# power-distribution.net
KiCad netlist of a schematic drawn in EAGLE
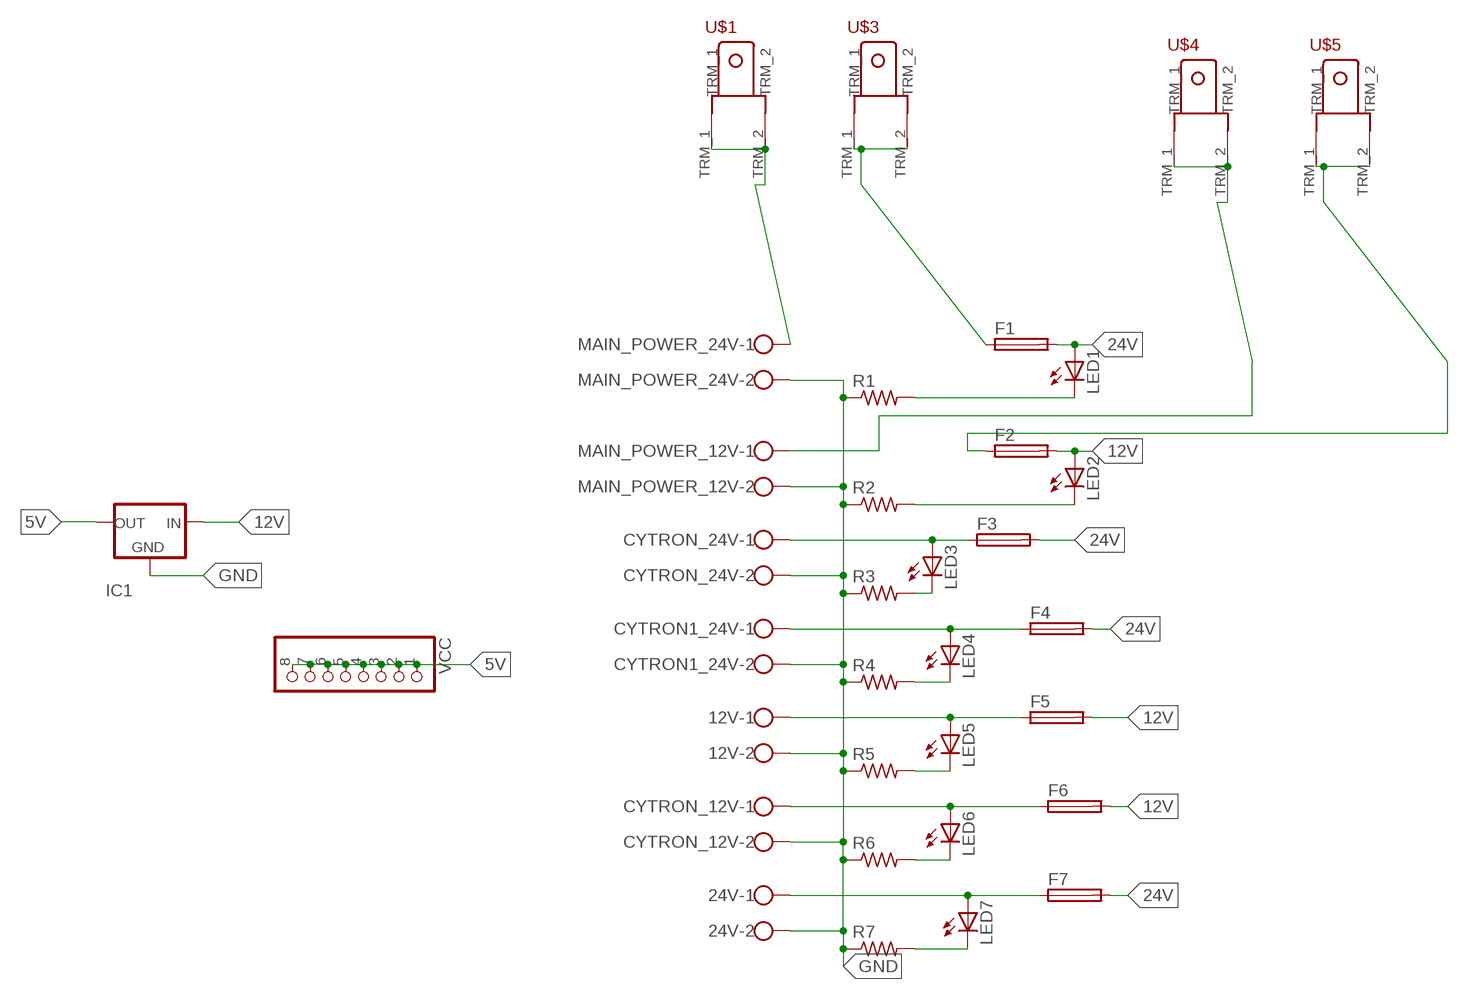
[diagram p0: schematic, sheet 1]

(export (version "E")
  (design (tool "Eeschema 10.0.6"))
  (components
    (comp (ref "12V")
      (value "W237-113")
      (footprint "eagle-import:W237-113")
      (libsource (lib "eagle-import") (part "W237-113"))
    )
    (comp (ref "24V")
      (value "W237-113")
      (footprint "eagle-import:W237-113")
      (libsource (lib "eagle-import") (part "W237-113"))
    )
    (comp (ref "CYTRON1_24V")
      (value "W237-113")
      (footprint "eagle-import:W237-113")
      (libsource (lib "eagle-import") (part "W237-113"))
    )
    (comp (ref "CYTRON_12V")
      (value "W237-113")
      (footprint "eagle-import:W237-113")
      (libsource (lib "eagle-import") (part "W237-113"))
    )
    (comp (ref "CYTRON_24V")
      (value "W237-113")
      (footprint "eagle-import:W237-113")
      (libsource (lib "eagle-import") (part "W237-113"))
    )
    (comp (ref "F1")
      (value "SH22,5A")
      (footprint "eagle-import:SH22,5A")
      (fields (field (name "MPN") "0031.7701.11"))
      (libsource (lib "eagle-import") (part "SH22,5A"))
    )
    (comp (ref "F2")
      (value "SH22,5A")
      (footprint "eagle-import:SH22,5A")
      (fields (field (name "MPN") "0031.7701.11"))
      (libsource (lib "eagle-import") (part "SH22,5A"))
    )
    (comp (ref "F3")
      (value "SH22,5A")
      (footprint "eagle-import:SH22,5A")
      (fields (field (name "MPN") "0031.7701.11"))
      (libsource (lib "eagle-import") (part "SH22,5A"))
    )
    (comp (ref "F4")
      (value "SH22,5A")
      (footprint "eagle-import:SH22,5A")
      (fields (field (name "MPN") "0031.7701.11"))
      (libsource (lib "eagle-import") (part "SH22,5A"))
    )
    (comp (ref "F5")
      (value "SH22,5A")
      (footprint "eagle-import:SH22,5A")
      (fields (field (name "MPN") "0031.7701.11"))
      (libsource (lib "eagle-import") (part "SH22,5A"))
    )
    (comp (ref "F6")
      (value "SH22,5A")
      (footprint "eagle-import:SH22,5A")
      (fields (field (name "MPN") "0031.7701.11"))
      (libsource (lib "eagle-import") (part "SH22,5A"))
    )
    (comp (ref "F7")
      (value "SH22,5A")
      (footprint "eagle-import:SH22,5A")
      (fields (field (name "MPN") "0031.7701.11"))
      (libsource (lib "eagle-import") (part "SH22,5A"))
    )
    (comp (ref "IC1")
      (value "79XX-TO3")
      (footprint "eagle-import:TO3-79")
      (libsource (lib "eagle-import") (part "79XX-TO3"))
    )
    (comp (ref "LED1")
      (value "LED5MM")
      (footprint "eagle-import:LED5MM")
      (libsource (lib "eagle-import") (part "LED5MM"))
    )
    (comp (ref "LED2")
      (value "LED5MM")
      (footprint "eagle-import:LED5MM")
      (libsource (lib "eagle-import") (part "LED5MM"))
    )
    (comp (ref "LED3")
      (value "LED3MM")
      (footprint "eagle-import:LED3MM")
      (libsource (lib "eagle-import") (part "LED3MM"))
    )
    (comp (ref "LED4")
      (value "LED3MM")
      (footprint "eagle-import:LED3MM")
      (libsource (lib "eagle-import") (part "LED3MM"))
    )
    (comp (ref "LED5")
      (value "LED3MM")
      (footprint "eagle-import:LED3MM")
      (libsource (lib "eagle-import") (part "LED3MM"))
    )
    (comp (ref "LED6")
      (value "LED3MM")
      (footprint "eagle-import:LED3MM")
      (libsource (lib "eagle-import") (part "LED3MM"))
    )
    (comp (ref "LED7")
      (value "LED3MM")
      (footprint "eagle-import:LED3MM")
      (libsource (lib "eagle-import") (part "LED3MM"))
    )
    (comp (ref "MAIN_POWER_12V")
      (value "W237-113")
      (footprint "eagle-import:W237-113")
      (libsource (lib "eagle-import") (part "W237-113"))
    )
    (comp (ref "MAIN_POWER_24V")
      (value "W237-113")
      (footprint "eagle-import:W237-113")
      (libsource (lib "eagle-import") (part "W237-113"))
    )
    (comp (ref "R1")
      (value "R-US_0204/5")
      (footprint "eagle-import:0204_5")
      (libsource (lib "eagle-import") (part "R-US_0204/5"))
    )
    (comp (ref "R2")
      (value "R-US_0207/12")
      (footprint "eagle-import:0207_12")
      (libsource (lib "eagle-import") (part "R-US_0207/12"))
    )
    (comp (ref "R3")
      (value "R-US_0204/5")
      (footprint "eagle-import:0204_5")
      (libsource (lib "eagle-import") (part "R-US_0204/5"))
    )
    (comp (ref "R4")
      (value "R-US_0204/5")
      (footprint "eagle-import:0204_5")
      (libsource (lib "eagle-import") (part "R-US_0204/5"))
    )
    (comp (ref "R5")
      (value "R-US_0207/10")
      (footprint "eagle-import:0207_10")
      (libsource (lib "eagle-import") (part "R-US_0207/10"))
    )
    (comp (ref "R6")
      (value "R-US_0204/5")
      (footprint "eagle-import:0204_5")
      (libsource (lib "eagle-import") (part "R-US_0204/5"))
    )
    (comp (ref "R7")
      (value "R-US_0204/5")
      (footprint "eagle-import:0204_5")
      (libsource (lib "eagle-import") (part "R-US_0204/5"))
    )
    (comp (ref "U$1")
      (value "TERMINAL_EDITED")
      (footprint "eagle-import:TERMINAL_EDITED")
      (libsource (lib "eagle-import") (part "TERMINAL_EDITED"))
    )
    (comp (ref "U$3")
      (value "TERMINAL_EDITED")
      (footprint "eagle-import:TERMINAL_EDITED")
      (libsource (lib "eagle-import") (part "TERMINAL_EDITED"))
    )
    (comp (ref "U$4")
      (value "TERMINAL_EDITED")
      (footprint "eagle-import:TERMINAL_EDITED")
      (libsource (lib "eagle-import") (part "TERMINAL_EDITED"))
    )
    (comp (ref "U$5")
      (value "TERMINAL_EDITED")
      (footprint "eagle-import:TERMINAL_EDITED")
      (libsource (lib "eagle-import") (part "TERMINAL_EDITED"))
    )
    (comp (ref "VCC")
      (value "PINHD-1X8")
      (footprint "eagle-import:1X08")
      (libsource (lib "eagle-import") (part "PINHD-1X8"))
    )
  )
  (nets
    (net (code "1") (name "5V") (class "Default")
      (node (ref "IC1") (pin "1") (pinfunction "OUT_1") (pintype "passive"))
      (node (ref "VCC") (pin "1") (pinfunction "1_1") (pintype "passive"))
      (node (ref "VCC") (pin "2") (pinfunction "2_2") (pintype "passive"))
      (node (ref "VCC") (pin "3") (pinfunction "3_3") (pintype "passive"))
      (node (ref "VCC") (pin "4") (pinfunction "4_4") (pintype "passive"))
      (node (ref "VCC") (pin "5") (pinfunction "5_5") (pintype "passive"))
      (node (ref "VCC") (pin "6") (pinfunction "6_6") (pintype "passive"))
      (node (ref "VCC") (pin "7") (pinfunction "7_7") (pintype "passive"))
      (node (ref "VCC") (pin "8") (pinfunction "8_8") (pintype "passive"))
    )
    (net (code "2") (name "12V") (class "Default")
      (node (ref "F2") (pin "2") (pinfunction "2_2") (pintype "passive"))
      (node (ref "F5") (pin "2") (pinfunction "2_2") (pintype "passive"))
      (node (ref "F6") (pin "2") (pinfunction "2_2") (pintype "passive"))
      (node (ref "IC1") (pin "3") (pinfunction "IN_3") (pintype "input"))
      (node (ref "LED2") (pin "A") (pinfunction "A_A") (pintype "passive"))
    )
    (net (code "3") (name "24V") (class "Default")
      (node (ref "F1") (pin "2") (pinfunction "2_2") (pintype "passive"))
      (node (ref "F3") (pin "2") (pinfunction "2_2") (pintype "passive"))
      (node (ref "F4") (pin "2") (pinfunction "2_2") (pintype "passive"))
      (node (ref "F7") (pin "2") (pinfunction "2_2") (pintype "passive"))
      (node (ref "LED1") (pin "A") (pinfunction "A_A") (pintype "passive"))
    )
    (net (code "4") (name "GND") (class "Default")
      (node (ref "12V") (pin "2") (pinfunction "KL_2") (pintype "passive"))
      (node (ref "24V") (pin "2") (pinfunction "KL_2") (pintype "passive"))
      (node (ref "CYTRON1_24V") (pin "2") (pinfunction "KL_2") (pintype "passive"))
      (node (ref "CYTRON_12V") (pin "2") (pinfunction "KL_2") (pintype "passive"))
      (node (ref "CYTRON_24V") (pin "2") (pinfunction "KL_2") (pintype "passive"))
      (node (ref "IC1") (pin "2") (pinfunction "GND_2") (pintype "input"))
      (node (ref "MAIN_POWER_12V") (pin "2") (pinfunction "KL_2") (pintype "passive"))
      (node (ref "MAIN_POWER_24V") (pin "2") (pinfunction "KL_2") (pintype "passive"))
      (node (ref "R1") (pin "1") (pinfunction "1_1") (pintype "passive"))
      (node (ref "R2") (pin "1") (pinfunction "1_1") (pintype "passive"))
      (node (ref "R3") (pin "1") (pinfunction "1_1") (pintype "passive"))
      (node (ref "R4") (pin "1") (pinfunction "1_1") (pintype "passive"))
      (node (ref "R5") (pin "1") (pinfunction "1_1") (pintype "passive"))
      (node (ref "R6") (pin "1") (pinfunction "1_1") (pintype "passive"))
      (node (ref "R7") (pin "1") (pinfunction "1_1") (pintype "passive"))
    )
    (net (code "5") (name "Net-(12VA-KL)") (class "Default")
      (node (ref "12V") (pin "1") (pinfunction "KL_1") (pintype "passive"))
      (node (ref "F5") (pin "1") (pinfunction "1_1") (pintype "passive"))
      (node (ref "LED5") (pin "A") (pinfunction "A_A") (pintype "passive"))
    )
    (net (code "6") (name "Net-(24VA-KL)") (class "Default")
      (node (ref "24V") (pin "1") (pinfunction "KL_1") (pintype "passive"))
      (node (ref "F7") (pin "1") (pinfunction "1_1") (pintype "passive"))
      (node (ref "LED7") (pin "A") (pinfunction "A_A") (pintype "passive"))
    )
    (net (code "7") (name "Net-(CYTRON1_24VA-KL)") (class "Default")
      (node (ref "CYTRON1_24V") (pin "1") (pinfunction "KL_1") (pintype "passive"))
      (node (ref "F4") (pin "1") (pinfunction "1_1") (pintype "passive"))
      (node (ref "LED4") (pin "A") (pinfunction "A_A") (pintype "passive"))
    )
    (net (code "8") (name "Net-(CYTRON_12VA-KL)") (class "Default")
      (node (ref "CYTRON_12V") (pin "1") (pinfunction "KL_1") (pintype "passive"))
      (node (ref "F6") (pin "1") (pinfunction "1_1") (pintype "passive"))
      (node (ref "LED6") (pin "A") (pinfunction "A_A") (pintype "passive"))
    )
    (net (code "9") (name "Net-(CYTRON_24VA-KL)") (class "Default")
      (node (ref "CYTRON_24V") (pin "1") (pinfunction "KL_1") (pintype "passive"))
      (node (ref "F3") (pin "1") (pinfunction "1_1") (pintype "passive"))
      (node (ref "LED3") (pin "A") (pinfunction "A_A") (pintype "passive"))
    )
    (net (code "10") (name "Net-(F1-Pad1)") (class "Default")
      (node (ref "F1") (pin "1") (pinfunction "1_1") (pintype "passive"))
      (node (ref "U$3") (pin "TRM_1") (pinfunction "TRM_1_TRM_1") (pintype "bidirectional"))
      (node (ref "U$3") (pin "TRM_2") (pinfunction "TRM_2_TRM_2") (pintype "bidirectional"))
    )
    (net (code "11") (name "Net-(F2-Pad1)") (class "Default")
      (node (ref "F2") (pin "1") (pinfunction "1_1") (pintype "passive"))
      (node (ref "U$5") (pin "TRM_1") (pinfunction "TRM_1_TRM_1") (pintype "bidirectional"))
      (node (ref "U$5") (pin "TRM_2") (pinfunction "TRM_2_TRM_2") (pintype "bidirectional"))
    )
    (net (code "12") (name "Net-(LED1-C)") (class "Default")
      (node (ref "LED1") (pin "K") (pinfunction "C_K") (pintype "passive"))
      (node (ref "R1") (pin "2") (pinfunction "2_2") (pintype "passive"))
    )
    (net (code "13") (name "Net-(LED2-C)") (class "Default")
      (node (ref "LED2") (pin "K") (pinfunction "C_K") (pintype "passive"))
      (node (ref "R2") (pin "2") (pinfunction "2_2") (pintype "passive"))
    )
    (net (code "14") (name "Net-(LED3-C)") (class "Default")
      (node (ref "LED3") (pin "K") (pinfunction "C_K") (pintype "passive"))
      (node (ref "R3") (pin "2") (pinfunction "2_2") (pintype "passive"))
    )
    (net (code "15") (name "Net-(LED4-C)") (class "Default")
      (node (ref "LED4") (pin "K") (pinfunction "C_K") (pintype "passive"))
      (node (ref "R4") (pin "2") (pinfunction "2_2") (pintype "passive"))
    )
    (net (code "16") (name "Net-(LED5-C)") (class "Default")
      (node (ref "LED5") (pin "K") (pinfunction "C_K") (pintype "passive"))
      (node (ref "R5") (pin "2") (pinfunction "2_2") (pintype "passive"))
    )
    (net (code "17") (name "Net-(LED6-C)") (class "Default")
      (node (ref "LED6") (pin "K") (pinfunction "C_K") (pintype "passive"))
      (node (ref "R6") (pin "2") (pinfunction "2_2") (pintype "passive"))
    )
    (net (code "18") (name "Net-(LED7-C)") (class "Default")
      (node (ref "LED7") (pin "K") (pinfunction "C_K") (pintype "passive"))
      (node (ref "R7") (pin "2") (pinfunction "2_2") (pintype "passive"))
    )
    (net (code "19") (name "Net-(MAIN_POWER_12VA-KL)") (class "Default")
      (node (ref "MAIN_POWER_12V") (pin "1") (pinfunction "KL_1") (pintype "passive"))
      (node (ref "U$4") (pin "TRM_1") (pinfunction "TRM_1_TRM_1") (pintype "bidirectional"))
      (node (ref "U$4") (pin "TRM_2") (pinfunction "TRM_2_TRM_2") (pintype "bidirectional"))
    )
    (net (code "20") (name "Net-(MAIN_POWER_24VA-KL)") (class "Default")
      (node (ref "MAIN_POWER_24V") (pin "1") (pinfunction "KL_1") (pintype "passive"))
      (node (ref "U$1") (pin "TRM_1") (pinfunction "TRM_1_TRM_1") (pintype "bidirectional"))
      (node (ref "U$1") (pin "TRM_2") (pinfunction "TRM_2_TRM_2") (pintype "bidirectional"))
    )
  )
)
